# 1-Microcontroller.net
KiCad netlist of a schematic drawn in Altium Designer
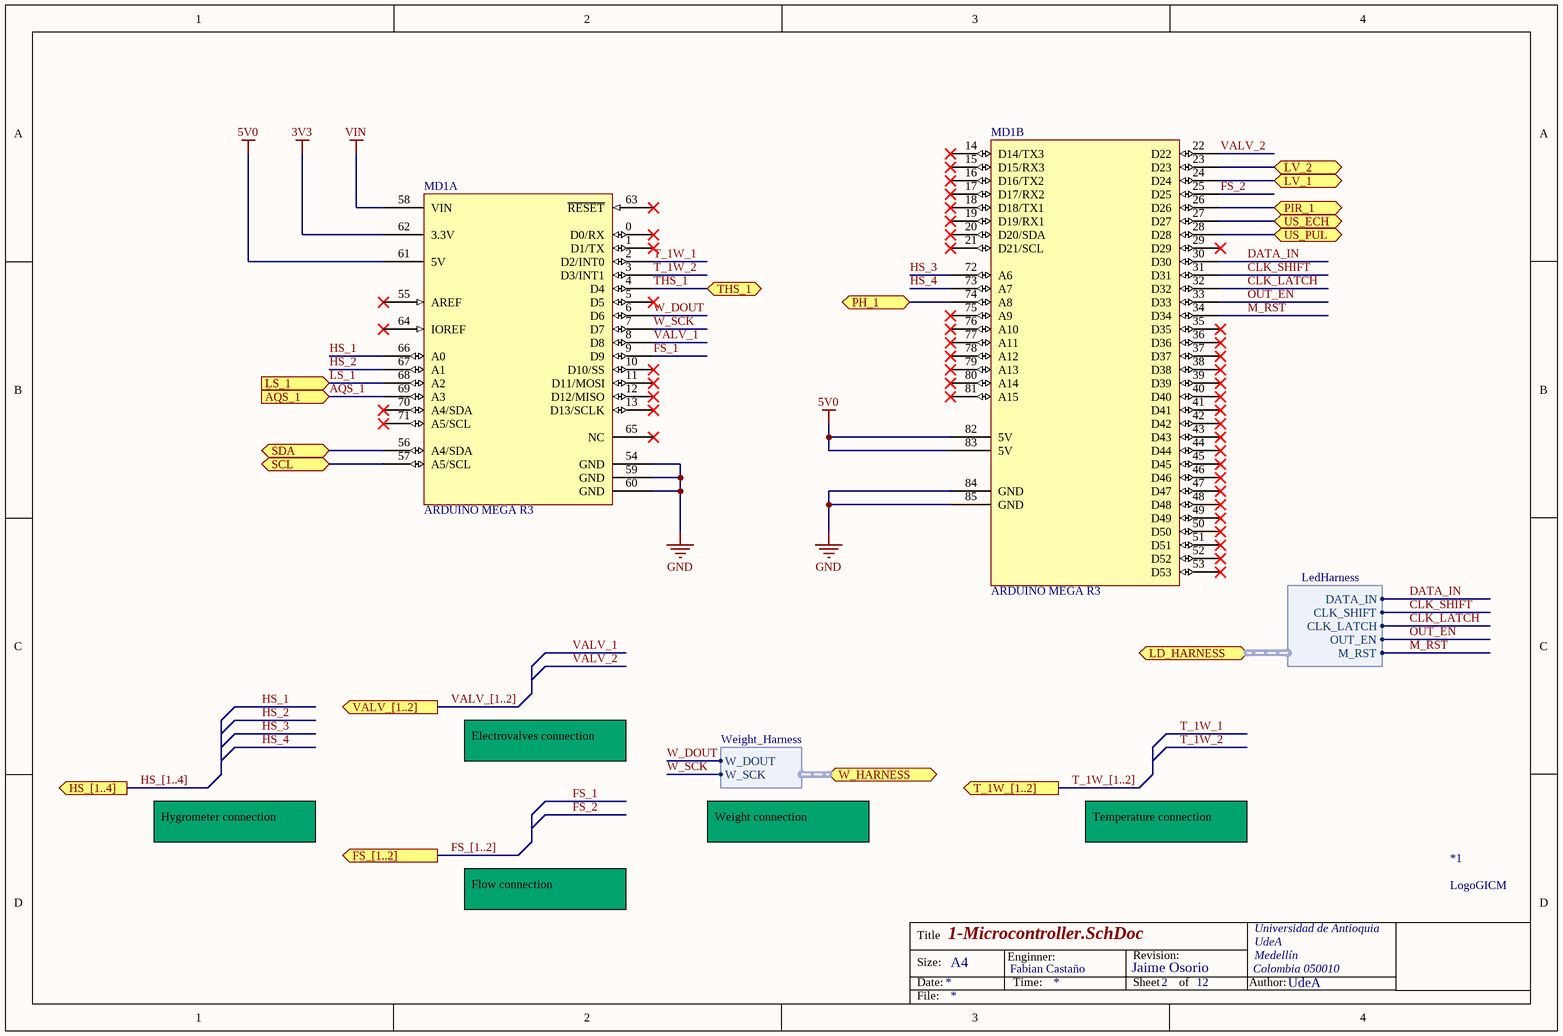
[diagram p0: 1-Microcontroller.SchDoc]

(export (version "E")
  (design (tool "Eeschema 10.0.6"))
  (components
    (comp (ref "*1") (value "LogoGICM") (footprint "LOGO") (libsource (lib "LogoGICM") (part "LogoGICM")))
    (comp (ref "MD1")
      (value "ARDUINO MEGA R3")
      (footprint "ArduinoMega")
      (libsource (lib "ArduinoMegaShield") (part "Arduino_Mega_R3"))
    )
  )
  (nets
    (net (code "3") (name "/AQS_1") (class "Default")
      (node (ref "MD1") (pin "69") (pinfunction "A3_69") (pintype "bidirectional"))
    )
    (net (code "4") (name "/CLK_LATCH") (class "Default")
      (node (ref "MD1") (pin "32") (pinfunction "D32_32") (pintype "bidirectional"))
    )
    (net (code "5") (name "/CLK_SHIFT") (class "Default")
      (node (ref "MD1") (pin "31") (pinfunction "D31_31") (pintype "bidirectional"))
    )
    (net (code "6") (name "/DATA_IN") (class "Default")
      (node (ref "MD1") (pin "30") (pinfunction "D30_30") (pintype "bidirectional"))
    )
    (net (code "7") (name "/FS_1") (class "Default")
      (node (ref "MD1") (pin "9") (pinfunction "D9_9") (pintype "bidirectional"))
    )
    (net (code "8") (name "/FS_2") (class "Default")
      (node (ref "MD1") (pin "25") (pinfunction "D25_25") (pintype "bidirectional"))
    )
    (net (code "10") (name "/HS_1") (class "Default")
      (node (ref "MD1") (pin "66") (pinfunction "A0_66") (pintype "bidirectional"))
    )
    (net (code "11") (name "/HS_2") (class "Default")
      (node (ref "MD1") (pin "67") (pinfunction "A1_67") (pintype "bidirectional"))
    )
    (net (code "12") (name "/HS_3") (class "Default")
      (node (ref "MD1") (pin "72") (pinfunction "A6_72") (pintype "bidirectional"))
    )
    (net (code "13") (name "/HS_4") (class "Default")
      (node (ref "MD1") (pin "73") (pinfunction "A7_73") (pintype "bidirectional"))
    )
    (net (code "15") (name "/LS_1") (class "Default")
      (node (ref "MD1") (pin "68") (pinfunction "A2_68") (pintype "bidirectional"))
    )
    (net (code "16") (name "/LV_1") (class "Default")
      (node (ref "MD1") (pin "24") (pinfunction "D24_24") (pintype "bidirectional"))
    )
    (net (code "17") (name "/LV_2") (class "Default")
      (node (ref "MD1") (pin "23") (pinfunction "D23_23") (pintype "bidirectional"))
    )
    (net (code "18") (name "/M_RST") (class "Default")
      (node (ref "MD1") (pin "34") (pinfunction "D34_34") (pintype "bidirectional"))
    )
    (net (code "19") (name "/OUT_EN") (class "Default")
      (node (ref "MD1") (pin "33") (pinfunction "D33_33") (pintype "bidirectional"))
    )
    (net (code "20") (name "/PH_1") (class "Default")
      (node (ref "MD1") (pin "74") (pinfunction "A8_74") (pintype "bidirectional"))
    )
    (net (code "21") (name "/PIR_1") (class "Default")
      (node (ref "MD1") (pin "26") (pinfunction "D26_26") (pintype "bidirectional"))
    )
    (net (code "22") (name "/SCL") (class "Default")
      (node (ref "MD1") (pin "57") (pinfunction "A5/SCL_57") (pintype "bidirectional"))
    )
    (net (code "23") (name "/SDA") (class "Default")
      (node (ref "MD1") (pin "56") (pinfunction "A4/SDA_56") (pintype "bidirectional"))
    )
    (net (code "24") (name "/THS_1") (class "Default")
      (node (ref "MD1") (pin "4") (pinfunction "D4_4") (pintype "bidirectional"))
    )
    (net (code "25") (name "/T_1W_1") (class "Default")
      (node (ref "MD1") (pin "2") (pinfunction "D2/INT0_2") (pintype "bidirectional"))
    )
    (net (code "26") (name "/T_1W_2") (class "Default")
      (node (ref "MD1") (pin "3") (pinfunction "D3/INT1_3") (pintype "bidirectional"))
    )
    (net (code "28") (name "/US_ECH") (class "Default")
      (node (ref "MD1") (pin "27") (pinfunction "D27_27") (pintype "bidirectional"))
    )
    (net (code "29") (name "/US_PUL") (class "Default")
      (node (ref "MD1") (pin "28") (pinfunction "D28_28") (pintype "bidirectional"))
    )
    (net (code "30") (name "/VALV_1") (class "Default")
      (node (ref "MD1") (pin "8") (pinfunction "D8_8") (pintype "bidirectional"))
    )
    (net (code "31") (name "/VALV_2") (class "Default")
      (node (ref "MD1") (pin "22") (pinfunction "D22_22") (pintype "bidirectional"))
    )
    (net (code "33") (name "/W_DOUT") (class "Default")
      (node (ref "MD1") (pin "6") (pinfunction "D6_6") (pintype "bidirectional"))
    )
    (net (code "34") (name "/W_SCK") (class "Default")
      (node (ref "MD1") (pin "7") (pinfunction "D7_7") (pintype "bidirectional"))
    )
    (net (code "37") (name "3V3") (class "Default")
      (node (ref "MD1") (pin "62") (pinfunction "3.3V_62") (pintype "power_in"))
    )
    (net (code "38") (name "5V0") (class "Default")
      (node (ref "MD1") (pin "61") (pinfunction "5V_61") (pintype "power_in"))
      (node (ref "MD1") (pin "82") (pinfunction "5V_82") (pintype "power_in"))
      (node (ref "MD1") (pin "83") (pinfunction "5V_83") (pintype "power_in"))
    )
    (net (code "39") (name "GND") (class "Default")
      (node (ref "MD1") (pin "54") (pinfunction "GND_54") (pintype "power_in"))
      (node (ref "MD1") (pin "59") (pinfunction "GND_59") (pintype "power_in"))
      (node (ref "MD1") (pin "60") (pinfunction "GND_60") (pintype "power_in"))
      (node (ref "MD1") (pin "84") (pinfunction "GND_84") (pintype "power_in"))
      (node (ref "MD1") (pin "85") (pinfunction "GND_85") (pintype "power_in"))
    )
    (net (code "40") (name "VIN") (class "Default")
      (node (ref "MD1") (pin "58") (pinfunction "VIN_58") (pintype "power_in"))
    )
    (net (code "41") (name "unconnected-(MD1A-A4{slash}SDA-Pad70)") (class "Default")
      (node (ref "MD1") (pin "70") (pinfunction "A4/SDA_70") (pintype "bidirectional+no_connect"))
    )
    (net (code "42") (name "unconnected-(MD1A-A5{slash}SCL-Pad71)") (class "Default")
      (node (ref "MD1") (pin "71") (pinfunction "A5/SCL_71") (pintype "bidirectional+no_connect"))
    )
    (net (code "43") (name "unconnected-(MD1A-AREF-Pad55)") (class "Default")
      (node (ref "MD1") (pin "55") (pinfunction "AREF_55") (pintype "input+no_connect"))
    )
    (net (code "44") (name "unconnected-(MD1A-D0{slash}RX-Pad0)") (class "Default")
      (node (ref "MD1") (pin "0") (pinfunction "D0/RX_0") (pintype "bidirectional+no_connect"))
    )
    (net (code "45") (name "unconnected-(MD1A-D1{slash}TX-Pad1)") (class "Default")
      (node (ref "MD1") (pin "1") (pinfunction "D1/TX_1") (pintype "bidirectional+no_connect"))
    )
    (net (code "46") (name "unconnected-(MD1A-D5-Pad5)") (class "Default")
      (node (ref "MD1") (pin "5") (pinfunction "D5_5") (pintype "bidirectional+no_connect"))
    )
    (net (code "47") (name "unconnected-(MD1A-D10{slash}SS-Pad10)") (class "Default")
      (node (ref "MD1") (pin "10") (pinfunction "D10/SS_10") (pintype "bidirectional+no_connect"))
    )
    (net (code "48") (name "unconnected-(MD1A-D11{slash}MOSI-Pad11)") (class "Default")
      (node (ref "MD1") (pin "11") (pinfunction "D11/MOSI_11") (pintype "bidirectional+no_connect"))
    )
    (net (code "49") (name "unconnected-(MD1A-D12{slash}MISO-Pad12)") (class "Default")
      (node (ref "MD1") (pin "12") (pinfunction "D12/MISO_12") (pintype "bidirectional+no_connect"))
    )
    (net (code "50") (name "unconnected-(MD1A-D13{slash}SCLK-Pad13)") (class "Default")
      (node (ref "MD1") (pin "13") (pinfunction "D13/SCLK_13") (pintype "bidirectional+no_connect"))
    )
    (net (code "51") (name "unconnected-(MD1A-IOREF-Pad64)") (class "Default")
      (node (ref "MD1") (pin "64") (pinfunction "IOREF_64") (pintype "input+no_connect"))
    )
    (net (code "52") (name "unconnected-(MD1A-NC-Pad65)") (class "Default")
      (node (ref "MD1") (pin "65") (pinfunction "NC_65") (pintype "passive+no_connect"))
    )
    (net (code "53") (name "unconnected-(MD1A-~{RESET}-Pad63)") (class "Default")
      (node (ref "MD1") (pin "63") (pinfunction "~{RESET}_63") (pintype "input+no_connect"))
    )
    (net (code "54") (name "unconnected-(MD1B-A9-Pad75)") (class "Default")
      (node (ref "MD1") (pin "75") (pinfunction "A9_75") (pintype "bidirectional+no_connect"))
    )
    (net (code "55") (name "unconnected-(MD1B-A10-Pad76)") (class "Default")
      (node (ref "MD1") (pin "76") (pinfunction "A10_76") (pintype "bidirectional+no_connect"))
    )
    (net (code "56") (name "unconnected-(MD1B-A11-Pad77)") (class "Default")
      (node (ref "MD1") (pin "77") (pinfunction "A11_77") (pintype "bidirectional+no_connect"))
    )
    (net (code "57") (name "unconnected-(MD1B-A12-Pad78)") (class "Default")
      (node (ref "MD1") (pin "78") (pinfunction "A12_78") (pintype "bidirectional+no_connect"))
    )
    (net (code "58") (name "unconnected-(MD1B-A13-Pad79)") (class "Default")
      (node (ref "MD1") (pin "79") (pinfunction "A13_79") (pintype "bidirectional+no_connect"))
    )
    (net (code "59") (name "unconnected-(MD1B-A14-Pad80)") (class "Default")
      (node (ref "MD1") (pin "80") (pinfunction "A14_80") (pintype "bidirectional+no_connect"))
    )
    (net (code "60") (name "unconnected-(MD1B-A15-Pad81)") (class "Default")
      (node (ref "MD1") (pin "81") (pinfunction "A15_81") (pintype "bidirectional+no_connect"))
    )
    (net (code "61") (name "unconnected-(MD1B-D14{slash}TX3-Pad14)") (class "Default")
      (node (ref "MD1") (pin "14") (pinfunction "D14/TX3_14") (pintype "bidirectional+no_connect"))
    )
    (net (code "62") (name "unconnected-(MD1B-D15{slash}RX3-Pad15)") (class "Default")
      (node (ref "MD1") (pin "15") (pinfunction "D15/RX3_15") (pintype "bidirectional+no_connect"))
    )
    (net (code "63") (name "unconnected-(MD1B-D16{slash}TX2-Pad16)") (class "Default")
      (node (ref "MD1") (pin "16") (pinfunction "D16/TX2_16") (pintype "bidirectional+no_connect"))
    )
    (net (code "64") (name "unconnected-(MD1B-D17{slash}RX2-Pad17)") (class "Default")
      (node (ref "MD1") (pin "17") (pinfunction "D17/RX2_17") (pintype "bidirectional+no_connect"))
    )
    (net (code "65") (name "unconnected-(MD1B-D18{slash}TX1-Pad18)") (class "Default")
      (node (ref "MD1") (pin "18") (pinfunction "D18/TX1_18") (pintype "bidirectional+no_connect"))
    )
    (net (code "66") (name "unconnected-(MD1B-D19{slash}RX1-Pad19)") (class "Default")
      (node (ref "MD1") (pin "19") (pinfunction "D19/RX1_19") (pintype "bidirectional+no_connect"))
    )
    (net (code "67") (name "unconnected-(MD1B-D20{slash}SDA-Pad20)") (class "Default")
      (node (ref "MD1") (pin "20") (pinfunction "D20/SDA_20") (pintype "bidirectional+no_connect"))
    )
    (net (code "68") (name "unconnected-(MD1B-D21{slash}SCL-Pad21)") (class "Default")
      (node (ref "MD1") (pin "21") (pinfunction "D21/SCL_21") (pintype "bidirectional+no_connect"))
    )
    (net (code "69") (name "unconnected-(MD1B-D29-Pad29)") (class "Default")
      (node (ref "MD1") (pin "29") (pinfunction "D29_29") (pintype "bidirectional+no_connect"))
    )
    (net (code "70") (name "unconnected-(MD1B-D35-Pad35)") (class "Default")
      (node (ref "MD1") (pin "35") (pinfunction "D35_35") (pintype "bidirectional+no_connect"))
    )
    (net (code "71") (name "unconnected-(MD1B-D36-Pad36)") (class "Default")
      (node (ref "MD1") (pin "36") (pinfunction "D36_36") (pintype "bidirectional+no_connect"))
    )
    (net (code "72") (name "unconnected-(MD1B-D37-Pad37)") (class "Default")
      (node (ref "MD1") (pin "37") (pinfunction "D37_37") (pintype "bidirectional+no_connect"))
    )
    (net (code "73") (name "unconnected-(MD1B-D38-Pad38)") (class "Default")
      (node (ref "MD1") (pin "38") (pinfunction "D38_38") (pintype "bidirectional+no_connect"))
    )
    (net (code "74") (name "unconnected-(MD1B-D39-Pad39)") (class "Default")
      (node (ref "MD1") (pin "39") (pinfunction "D39_39") (pintype "bidirectional+no_connect"))
    )
    (net (code "75") (name "unconnected-(MD1B-D40-Pad40)") (class "Default")
      (node (ref "MD1") (pin "40") (pinfunction "D40_40") (pintype "bidirectional+no_connect"))
    )
    (net (code "76") (name "unconnected-(MD1B-D41-Pad41)") (class "Default")
      (node (ref "MD1") (pin "41") (pinfunction "D41_41") (pintype "bidirectional+no_connect"))
    )
    (net (code "77") (name "unconnected-(MD1B-D42-Pad42)") (class "Default")
      (node (ref "MD1") (pin "42") (pinfunction "D42_42") (pintype "bidirectional+no_connect"))
    )
    (net (code "78") (name "unconnected-(MD1B-D43-Pad43)") (class "Default")
      (node (ref "MD1") (pin "43") (pinfunction "D43_43") (pintype "bidirectional+no_connect"))
    )
    (net (code "79") (name "unconnected-(MD1B-D44-Pad44)") (class "Default")
      (node (ref "MD1") (pin "44") (pinfunction "D44_44") (pintype "bidirectional+no_connect"))
    )
    (net (code "80") (name "unconnected-(MD1B-D45-Pad45)") (class "Default")
      (node (ref "MD1") (pin "45") (pinfunction "D45_45") (pintype "bidirectional+no_connect"))
    )
    (net (code "81") (name "unconnected-(MD1B-D46-Pad46)") (class "Default")
      (node (ref "MD1") (pin "46") (pinfunction "D46_46") (pintype "bidirectional+no_connect"))
    )
    (net (code "82") (name "unconnected-(MD1B-D47-Pad47)") (class "Default")
      (node (ref "MD1") (pin "47") (pinfunction "D47_47") (pintype "bidirectional+no_connect"))
    )
    (net (code "83") (name "unconnected-(MD1B-D48-Pad48)") (class "Default")
      (node (ref "MD1") (pin "48") (pinfunction "D48_48") (pintype "bidirectional+no_connect"))
    )
    (net (code "84") (name "unconnected-(MD1B-D49-Pad49)") (class "Default")
      (node (ref "MD1") (pin "49") (pinfunction "D49_49") (pintype "bidirectional+no_connect"))
    )
    (net (code "85") (name "unconnected-(MD1B-D50-Pad50)") (class "Default")
      (node (ref "MD1") (pin "50") (pinfunction "D50_50") (pintype "bidirectional+no_connect"))
    )
    (net (code "86") (name "unconnected-(MD1B-D51-Pad51)") (class "Default")
      (node (ref "MD1") (pin "51") (pinfunction "D51_51") (pintype "bidirectional+no_connect"))
    )
    (net (code "87") (name "unconnected-(MD1B-D52-Pad52)") (class "Default")
      (node (ref "MD1") (pin "52") (pinfunction "D52_52") (pintype "bidirectional+no_connect"))
    )
    (net (code "88") (name "unconnected-(MD1B-D53-Pad53)") (class "Default")
      (node (ref "MD1") (pin "53") (pinfunction "D53_53") (pintype "bidirectional+no_connect"))
    )
  )
)
